# POE_PD_4_P-Schalter_minimized2.net
KiCad netlist of a schematic drawn in EAGLE
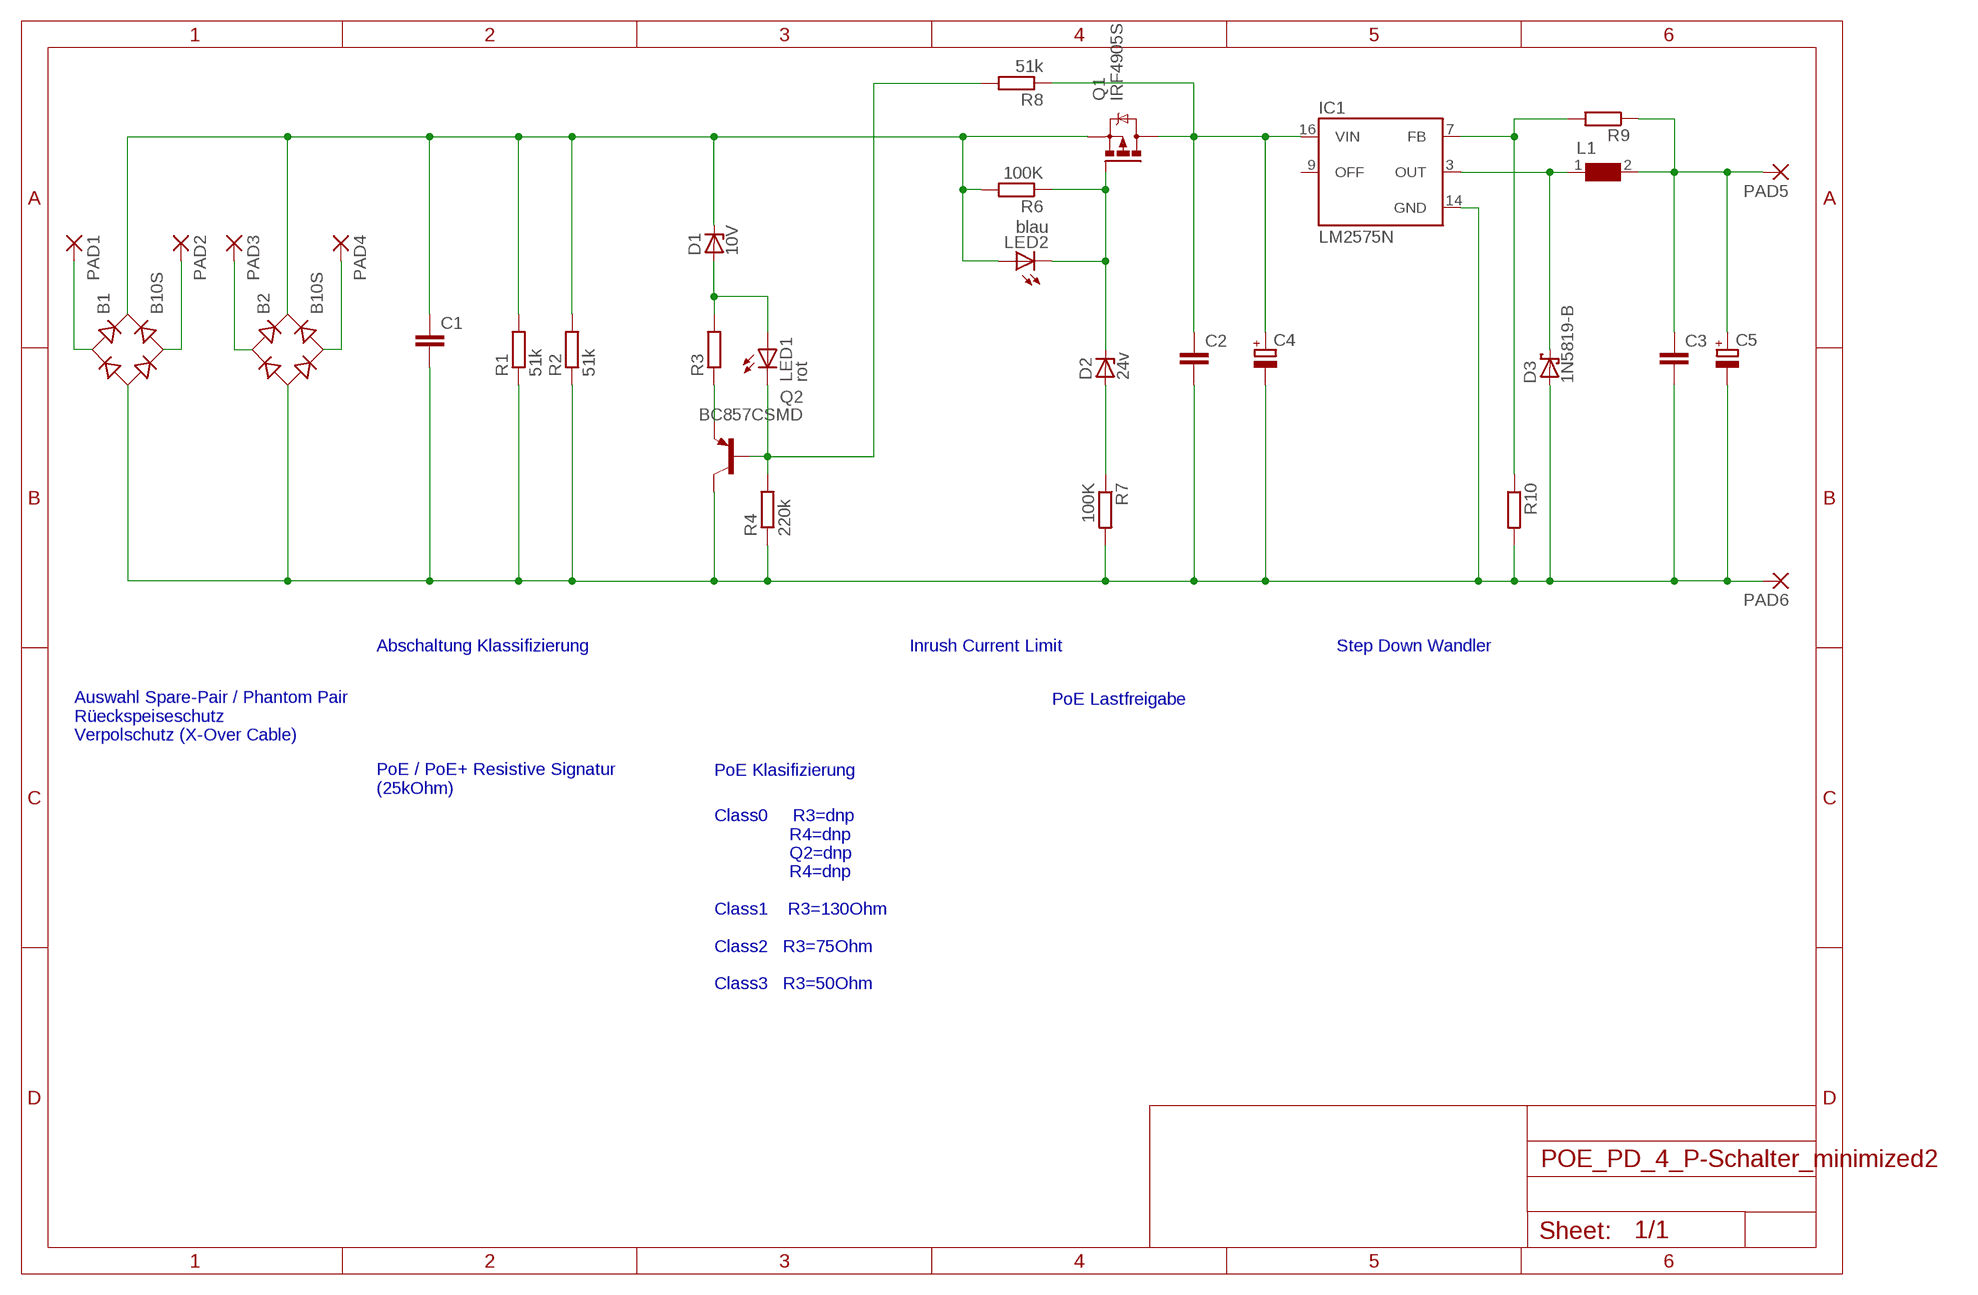
[diagram p0: schematic, sheet 1]

(export (version "E")
  (design (tool "Eeschema 10.0.6"))
  (components
    (comp (ref "B1")
      (value "B10S")
      (footprint "eagle-import:MBS")
      (libsource (lib "eagle-import") (part "BS10"))
    )
    (comp (ref "B2")
      (value "B10S")
      (footprint "eagle-import:MBS")
      (libsource (lib "eagle-import") (part "BS10"))
    )
    (comp (ref "C1")
      (value "C-EUC0805")
      (footprint "eagle-import:C0805")
      (libsource (lib "eagle-import") (part "C-EUC0805"))
    )
    (comp (ref "C2")
      (value "C-EUC0805")
      (footprint "eagle-import:C0805")
      (libsource (lib "eagle-import") (part "C-EUC0805"))
    )
    (comp (ref "C3")
      (value "C-EUC0805")
      (footprint "eagle-import:C0805")
      (libsource (lib "eagle-import") (part "C-EUC0805"))
    )
    (comp (ref "C4")
      (value "CPOL-EUE2.5-5")
      (footprint "eagle-import:E2,5-5")
      (libsource (lib "eagle-import") (part "CPOL-EUE2.5-5"))
    )
    (comp (ref "C5")
      (value "CPOL-EUE2.5-5")
      (footprint "eagle-import:E2,5-5")
      (libsource (lib "eagle-import") (part "CPOL-EUE2.5-5"))
    )
    (comp (ref "D1")
      (value "10V")
      (footprint "eagle-import:SOT23")
      (libsource (lib "eagle-import") (part "ZENER-DIODESOT23"))
    )
    (comp (ref "D2")
      (value "24v")
      (footprint "eagle-import:SOT23")
      (libsource (lib "eagle-import") (part "ZENER-DIODESOT23"))
    )
    (comp (ref "D3")
      (value "1N5819-B")
      (footprint "eagle-import:DO41-7.6")
      (libsource (lib "eagle-import") (part "1N5819-B"))
    )
    (comp (ref "IC1")
      (value "LM2575N")
      (footprint "eagle-import:DIL16")
      (libsource (lib "eagle-import") (part "LM2575N"))
    )
    (comp (ref "L1")
      (value "WE-PD2_S")
      (footprint "eagle-import:WE-PD2_S")
      (libsource (lib "eagle-import") (part "WE-PD2_S"))
    )
    (comp (ref "LED1")
      (value "rot")
      (footprint "eagle-import:CHIP-LED0805")
      (libsource (lib "eagle-import") (part "LEDCHIP-LED0805"))
    )
    (comp (ref "LED2")
      (value "blau")
      (footprint "eagle-import:CHIP-LED0805")
      (libsource (lib "eagle-import") (part "LEDCHIP-LED0805"))
    )
    (comp (ref "PAD1")
      (value "2,15/1,0")
      (footprint "eagle-import:2,15_1,0")
      (libsource (lib "eagle-import") (part "2,15/1,0"))
    )
    (comp (ref "PAD2")
      (value "2,15/1,0")
      (footprint "eagle-import:2,15_1,0")
      (libsource (lib "eagle-import") (part "2,15/1,0"))
    )
    (comp (ref "PAD3")
      (value "2,15/1,0")
      (footprint "eagle-import:2,15_1,0")
      (libsource (lib "eagle-import") (part "2,15/1,0"))
    )
    (comp (ref "PAD4")
      (value "2,15/1,0")
      (footprint "eagle-import:2,15_1,0")
      (libsource (lib "eagle-import") (part "2,15/1,0"))
    )
    (comp (ref "PAD5")
      (value "2,15/1,0")
      (footprint "eagle-import:2,15_1,0")
      (libsource (lib "eagle-import") (part "2,15/1,0"))
    )
    (comp (ref "PAD6")
      (value "2,15/1,0")
      (footprint "eagle-import:2,15_1,0")
      (libsource (lib "eagle-import") (part "2,15/1,0"))
    )
    (comp (ref "Q1")
      (value "IRF4905S")
      (footprint "eagle-import:D-PAK_TO252AA")
      (libsource (lib "eagle-import") (part "IRF?5305R"))
    )
    (comp (ref "Q2")
      (value "BC857CSMD")
      (footprint "eagle-import:SOT23-BEC")
      (libsource (lib "eagle-import") (part "BC857SMDC"))
    )
    (comp (ref "R1")
      (value "51k")
      (footprint "eagle-import:R0603")
      (libsource (lib "eagle-import") (part "R-EU_R0603"))
    )
    (comp (ref "R2")
      (value "51k")
      (footprint "eagle-import:R0603")
      (libsource (lib "eagle-import") (part "R-EU_R0603"))
    )
    (comp (ref "R3")
      (value "R-EU_0207/7")
      (footprint "eagle-import:0207_7")
      (libsource (lib "eagle-import") (part "R-EU_0207/7"))
    )
    (comp (ref "R4")
      (value "220k")
      (footprint "eagle-import:R0603")
      (libsource (lib "eagle-import") (part "R-EU_R0603"))
    )
    (comp (ref "R6")
      (value "100K")
      (footprint "eagle-import:R0603")
      (libsource (lib "eagle-import") (part "R-EU_R0603"))
    )
    (comp (ref "R7")
      (value "100K")
      (footprint "eagle-import:R0603")
      (libsource (lib "eagle-import") (part "R-EU_R0603"))
    )
    (comp (ref "R8")
      (value "51k")
      (footprint "eagle-import:R0603")
      (libsource (lib "eagle-import") (part "R-EU_R0603"))
    )
    (comp (ref "R9")
      (value "R-EU_0207/7")
      (footprint "eagle-import:0207_7")
      (libsource (lib "eagle-import") (part "R-EU_0207/7"))
    )
    (comp (ref "R10")
      (value "R-EU_0207/7")
      (footprint "eagle-import:0207_7")
      (libsource (lib "eagle-import") (part "R-EU_0207/7"))
    )
  )
  (nets
    (net (code "1") (name "Net-(D1-A)") (class "Default")
      (node (ref "D1") (pin "1") (pinfunction "A_1") (pintype "passive"))
      (node (ref "LED1") (pin "A") (pinfunction "A_A") (pintype "passive"))
      (node (ref "R3") (pin "2") (pinfunction "2_2") (pintype "passive"))
    )
    (net (code "2") (name "Net-(D1-C)") (class "Default")
      (node (ref "B1") (pin "+") (pinfunction "+_+") (pintype "passive"))
      (node (ref "B2") (pin "+") (pinfunction "+_+") (pintype "passive"))
      (node (ref "C1") (pin "1") (pinfunction "1_1") (pintype "passive"))
      (node (ref "D1") (pin "3") (pinfunction "C_3") (pintype "passive"))
      (node (ref "LED2") (pin "A") (pinfunction "A_A") (pintype "passive"))
      (node (ref "Q1") (pin "3") (pinfunction "S_3") (pintype "passive"))
      (node (ref "R1") (pin "2") (pinfunction "2_2") (pintype "passive"))
      (node (ref "R2") (pin "2") (pinfunction "2_2") (pintype "passive"))
      (node (ref "R6") (pin "2") (pinfunction "2_2") (pintype "passive"))
    )
    (net (code "3") (name "Net-(D2-A)") (class "Default")
      (node (ref "D2") (pin "1") (pinfunction "A_1") (pintype "passive"))
      (node (ref "R7") (pin "1") (pinfunction "1_1") (pintype "passive"))
    )
    (net (code "4") (name "Net-(D2-C)") (class "Default")
      (node (ref "D2") (pin "3") (pinfunction "C_3") (pintype "passive"))
      (node (ref "LED2") (pin "C") (pinfunction "C_C") (pintype "passive"))
      (node (ref "Q1") (pin "1") (pinfunction "G_1") (pintype "passive"))
      (node (ref "R6") (pin "1") (pinfunction "1_1") (pintype "passive"))
    )
    (net (code "5") (name "Net-(IC1-FB)") (class "Default")
      (node (ref "IC1") (pin "7") (pinfunction "FB_7") (pintype "input"))
      (node (ref "R10") (pin "1") (pinfunction "1_1") (pintype "passive"))
      (node (ref "R9") (pin "2") (pinfunction "2_2") (pintype "passive"))
    )
    (net (code "6") (name "Net-(IC1-GND)") (class "Default")
      (node (ref "B1") (pin "-") (pinfunction "-_-") (pintype "passive"))
      (node (ref "B2") (pin "-") (pinfunction "-_-") (pintype "passive"))
      (node (ref "C1") (pin "2") (pinfunction "2_2") (pintype "passive"))
      (node (ref "C2") (pin "2") (pinfunction "2_2") (pintype "passive"))
      (node (ref "C3") (pin "2") (pinfunction "2_2") (pintype "passive"))
      (node (ref "C4") (pin "-") (pinfunction "-_-") (pintype "passive"))
      (node (ref "C5") (pin "-") (pinfunction "-_-") (pintype "passive"))
      (node (ref "D3") (pin "A") (pinfunction "A_A") (pintype "passive"))
      (node (ref "IC1") (pin "14") (pinfunction "GND_14") (pintype "power_in"))
      (node (ref "PAD6") (pin "1") (pinfunction "P_1") (pintype "passive"))
      (node (ref "Q2") (pin "C") (pinfunction "C_C") (pintype "passive"))
      (node (ref "R1") (pin "1") (pinfunction "1_1") (pintype "passive"))
      (node (ref "R10") (pin "2") (pinfunction "2_2") (pintype "passive"))
      (node (ref "R2") (pin "1") (pinfunction "1_1") (pintype "passive"))
      (node (ref "R4") (pin "1") (pinfunction "1_1") (pintype "passive"))
      (node (ref "R7") (pin "2") (pinfunction "2_2") (pintype "passive"))
    )
    (net (code "7") (name "Net-(IC1-OUT)") (class "Default")
      (node (ref "D3") (pin "C") (pinfunction "C_C") (pintype "passive"))
      (node (ref "IC1") (pin "3") (pinfunction "OUT_3") (pintype "output"))
      (node (ref "L1") (pin "1") (pinfunction "1_1") (pintype "passive"))
    )
    (net (code "8") (name "Net-(IC1-VIN)") (class "Default")
      (node (ref "C2") (pin "1") (pinfunction "1_1") (pintype "passive"))
      (node (ref "C4") (pin "+") (pinfunction "+_+") (pintype "passive"))
      (node (ref "IC1") (pin "16") (pinfunction "VIN_16") (pintype "power_in"))
      (node (ref "Q1") (pin "4") (pinfunction "D_4") (pintype "passive"))
      (node (ref "R8") (pin "1") (pinfunction "1_1") (pintype "passive"))
    )
    (net (code "9") (name "Net-(LED1-PadC)") (class "Default")
      (node (ref "LED1") (pin "C") (pinfunction "C_C") (pintype "passive"))
      (node (ref "Q2") (pin "B") (pinfunction "B_B") (pintype "passive"))
      (node (ref "R4") (pin "2") (pinfunction "2_2") (pintype "passive"))
      (node (ref "R8") (pin "2") (pinfunction "2_2") (pintype "passive"))
    )
    (net (code "10") (name "Net-(PAD1-P)") (class "Default")
      (node (ref "B1") (pin "AC1") (pinfunction "AC1_AC1") (pintype "passive"))
      (node (ref "PAD1") (pin "1") (pinfunction "P_1") (pintype "passive"))
    )
    (net (code "11") (name "Net-(PAD2-P)") (class "Default")
      (node (ref "B1") (pin "AC2") (pinfunction "AC2_AC2") (pintype "passive"))
      (node (ref "PAD2") (pin "1") (pinfunction "P_1") (pintype "passive"))
    )
    (net (code "12") (name "Net-(PAD3-P)") (class "Default")
      (node (ref "B2") (pin "AC1") (pinfunction "AC1_AC1") (pintype "passive"))
      (node (ref "PAD3") (pin "1") (pinfunction "P_1") (pintype "passive"))
    )
    (net (code "13") (name "Net-(PAD4-P)") (class "Default")
      (node (ref "B2") (pin "AC2") (pinfunction "AC2_AC2") (pintype "passive"))
      (node (ref "PAD4") (pin "1") (pinfunction "P_1") (pintype "passive"))
    )
    (net (code "14") (name "Net-(PAD5-P)") (class "Default")
      (node (ref "C3") (pin "1") (pinfunction "1_1") (pintype "passive"))
      (node (ref "C5") (pin "+") (pinfunction "+_+") (pintype "passive"))
      (node (ref "L1") (pin "2") (pinfunction "2_2") (pintype "passive"))
      (node (ref "PAD5") (pin "1") (pinfunction "P_1") (pintype "passive"))
      (node (ref "R9") (pin "1") (pinfunction "1_1") (pintype "passive"))
    )
    (net (code "15") (name "Net-(Q2-PadE)") (class "Default")
      (node (ref "Q2") (pin "E") (pinfunction "E_E") (pintype "passive"))
      (node (ref "R3") (pin "1") (pinfunction "1_1") (pintype "passive"))
    )
    (net (code "16") (name "unconnected-(IC1-OFF-Pad9)") (class "Default")
      (node (ref "IC1") (pin "9") (pinfunction "OFF_9") (pintype "input"))
    )
  )
)
